# LPCB220_-_CORE_A.net
KiCad netlist of a schematic drawn in Altium Designer
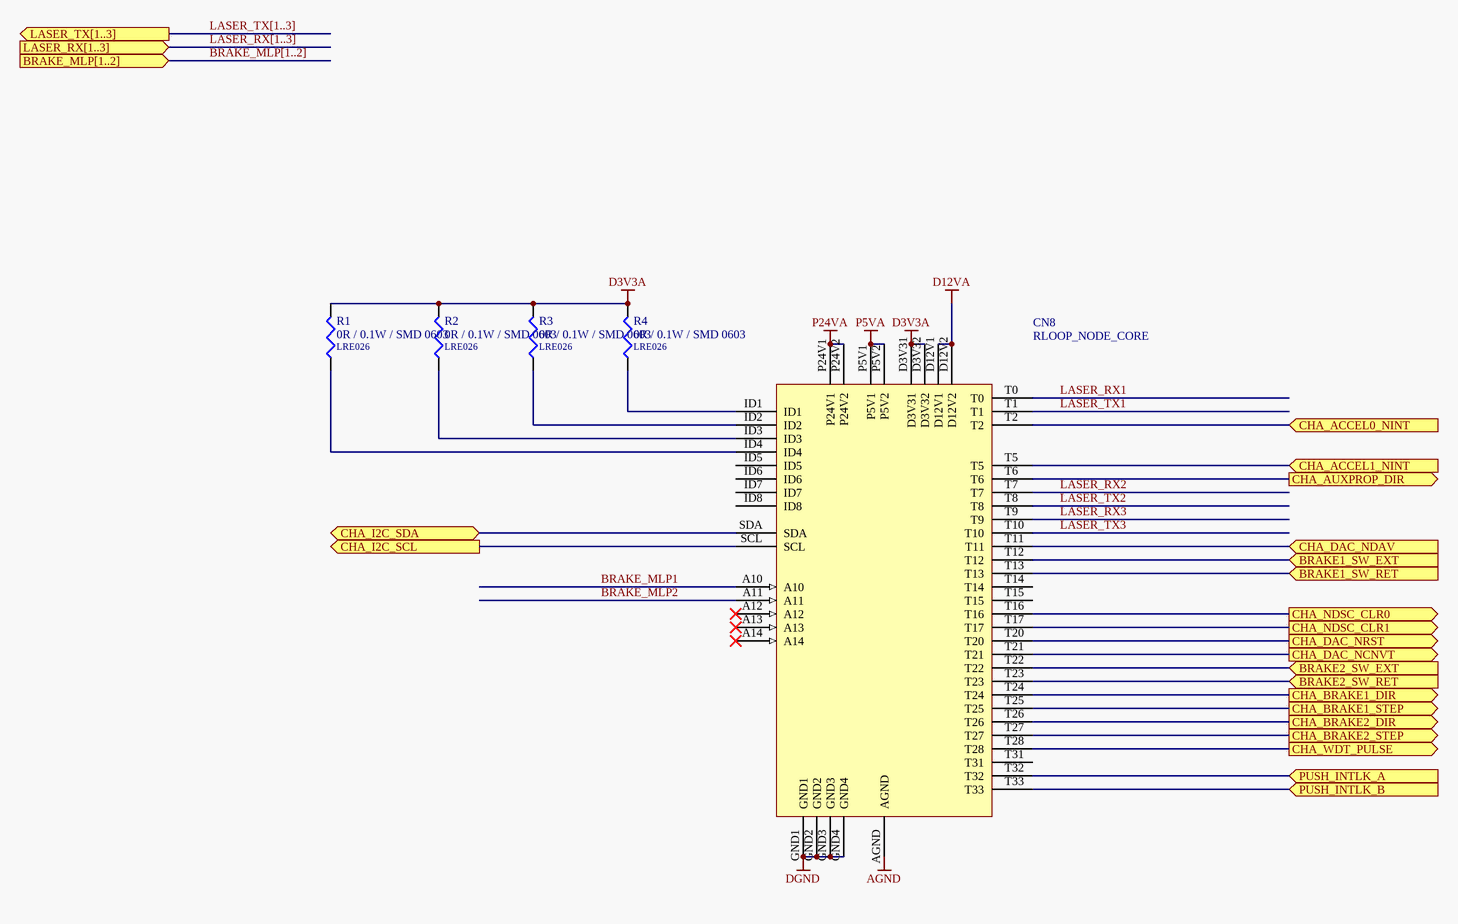
[diagram p0: LPCB220 - CORE A.SchDoc]

(export (version "E")
  (design (tool "Eeschema 10.0.6"))
  (components
    (comp (ref "CN8")
      (value "RLOOP_NODE_CORE")
      (footprint "RLOOP_NODE_CORE")
      (description "rLoop Node Core Connector")
      (libsource (lib "LDL_Connectors") (part "RLOOP_NODE_CORE"))
    )
    (comp (ref "R1")
      (value "0R / 0.1W / SMD 0603")
      (footprint "LFP020__CR1608-0603-IPC7351_B")
      (description "Resistor, Ceramic Chip, 0R, 0.1W, SMD 0603 [LRE026]")
      (fields (field (name "LDL_NUMBER") "LRE026"))
      (libsource (lib "LDL_Resistors") (part "0R / 0.1W / SMD 0603"))
    )
    (comp (ref "R2")
      (value "0R / 0.1W / SMD 0603")
      (footprint "LFP020__CR1608-0603-IPC7351_B")
      (description "Resistor, Ceramic Chip, 0R, 0.1W, SMD 0603 [LRE026]")
      (fields (field (name "LDL_NUMBER") "LRE026"))
      (libsource (lib "LDL_Resistors") (part "0R / 0.1W / SMD 0603"))
    )
    (comp (ref "R3")
      (value "0R / 0.1W / SMD 0603")
      (footprint "LFP020__CR1608-0603-IPC7351_B")
      (description "Resistor, Ceramic Chip, 0R, 0.1W, SMD 0603 [LRE026]")
      (fields (field (name "LDL_NUMBER") "LRE026"))
      (libsource (lib "LDL_Resistors") (part "0R / 0.1W / SMD 0603"))
    )
    (comp (ref "R4")
      (value "0R / 0.1W / SMD 0603")
      (footprint "LFP020__CR1608-0603-IPC7351_B")
      (description "Resistor, Ceramic Chip, 0R, 0.1W, SMD 0603 [LRE026]")
      (fields (field (name "LDL_NUMBER") "LRE026"))
      (libsource (lib "LDL_Resistors") (part "0R / 0.1W / SMD 0603"))
    )
  )
  (nets
    (net (code "1") (name "/BRAKE1_SW_EXT") (class "Default")
      (node (ref "CN8") (pin "T12") (pinfunction "T12_T12") (pintype "passive"))
    )
    (net (code "2") (name "/BRAKE1_SW_RET") (class "Default")
      (node (ref "CN8") (pin "T13") (pinfunction "T13_T13") (pintype "passive"))
    )
    (net (code "3") (name "/BRAKE2_SW_EXT") (class "Default")
      (node (ref "CN8") (pin "T22") (pinfunction "T22_T22") (pintype "passive"))
    )
    (net (code "4") (name "/BRAKE2_SW_RET") (class "Default")
      (node (ref "CN8") (pin "T23") (pinfunction "T23_T23") (pintype "passive"))
    )
    (net (code "5") (name "/BRAKE_MLP1") (class "Default")
      (node (ref "CN8") (pin "A10") (pinfunction "A10_A10") (pintype "input"))
    )
    (net (code "6") (name "/BRAKE_MLP2") (class "Default")
      (node (ref "CN8") (pin "A11") (pinfunction "A11_A11") (pintype "input"))
    )
    (net (code "8") (name "/CHA_ACCEL0_NINT") (class "Default")
      (node (ref "CN8") (pin "T2") (pinfunction "T2_T2") (pintype "passive"))
    )
    (net (code "9") (name "/CHA_ACCEL1_NINT") (class "Default")
      (node (ref "CN8") (pin "T5") (pinfunction "T5_T5") (pintype "passive"))
    )
    (net (code "10") (name "/CHA_AUXPROP_DIR") (class "Default")
      (node (ref "CN8") (pin "T6") (pinfunction "T6_T6") (pintype "passive"))
    )
    (net (code "11") (name "/CHA_BRAKE1_DIR") (class "Default")
      (node (ref "CN8") (pin "T24") (pinfunction "T24_T24") (pintype "passive"))
    )
    (net (code "12") (name "/CHA_BRAKE1_STEP") (class "Default")
      (node (ref "CN8") (pin "T25") (pinfunction "T25_T25") (pintype "passive"))
    )
    (net (code "13") (name "/CHA_BRAKE2_DIR") (class "Default")
      (node (ref "CN8") (pin "T26") (pinfunction "T26_T26") (pintype "passive"))
    )
    (net (code "14") (name "/CHA_BRAKE2_STEP") (class "Default")
      (node (ref "CN8") (pin "T27") (pinfunction "T27_T27") (pintype "passive"))
    )
    (net (code "15") (name "/CHA_DAC_NCNVT") (class "Default")
      (node (ref "CN8") (pin "T21") (pinfunction "T21_T21") (pintype "passive"))
    )
    (net (code "16") (name "/CHA_DAC_NDAV") (class "Default")
      (node (ref "CN8") (pin "T11") (pinfunction "T11_T11") (pintype "passive"))
    )
    (net (code "17") (name "/CHA_DAC_NRST") (class "Default")
      (node (ref "CN8") (pin "T20") (pinfunction "T20_T20") (pintype "passive"))
    )
    (net (code "18") (name "/CHA_I2C_SCL") (class "Default")
      (node (ref "CN8") (pin "SCL") (pinfunction "SCL_SCL") (pintype "passive"))
    )
    (net (code "19") (name "/CHA_I2C_SDA") (class "Default")
      (node (ref "CN8") (pin "SDA") (pinfunction "SDA_SDA") (pintype "passive"))
    )
    (net (code "20") (name "/CHA_NDSC_CLR0") (class "Default")
      (node (ref "CN8") (pin "T16") (pinfunction "T16_T16") (pintype "passive"))
    )
    (net (code "21") (name "/CHA_NDSC_CLR1") (class "Default")
      (node (ref "CN8") (pin "T17") (pinfunction "T17_T17") (pintype "passive"))
    )
    (net (code "22") (name "/CHA_WDT_PULSE") (class "Default")
      (node (ref "CN8") (pin "T28") (pinfunction "T28_T28") (pintype "passive"))
    )
    (net (code "23") (name "/LASER_RX1") (class "Default")
      (node (ref "CN8") (pin "T0") (pinfunction "T0_T0") (pintype "passive"))
    )
    (net (code "24") (name "/LASER_RX2") (class "Default")
      (node (ref "CN8") (pin "T7") (pinfunction "T7_T7") (pintype "passive"))
    )
    (net (code "25") (name "/LASER_RX3") (class "Default")
      (node (ref "CN8") (pin "T9") (pinfunction "T9_T9") (pintype "passive"))
    )
    (net (code "27") (name "/LASER_TX1") (class "Default")
      (node (ref "CN8") (pin "T1") (pinfunction "T1_T1") (pintype "passive"))
    )
    (net (code "28") (name "/LASER_TX2") (class "Default")
      (node (ref "CN8") (pin "T8") (pinfunction "T8_T8") (pintype "passive"))
    )
    (net (code "29") (name "/LASER_TX3") (class "Default")
      (node (ref "CN8") (pin "T10") (pinfunction "T10_T10") (pintype "passive"))
    )
    (net (code "31") (name "/PUSH_INTLK_A") (class "Default")
      (node (ref "CN8") (pin "T32") (pinfunction "T32_T32") (pintype "passive"))
    )
    (net (code "32") (name "/PUSH_INTLK_B") (class "Default")
      (node (ref "CN8") (pin "T33") (pinfunction "T33_T33") (pintype "passive"))
    )
    (net (code "33") (name "AGND") (class "Default")
      (node (ref "CN8") (pin "AGND") (pinfunction "AGND_AGND") (pintype "power_in"))
    )
    (net (code "34") (name "D3V3A") (class "Default")
      (node (ref "CN8") (pin "D3V31") (pinfunction "D3V31_D3V31") (pintype "power_in"))
      (node (ref "CN8") (pin "D3V32") (pinfunction "D3V32_D3V32") (pintype "power_in"))
      (node (ref "R1") (pin "2") (pintype "passive"))
      (node (ref "R2") (pin "2") (pintype "passive"))
      (node (ref "R3") (pin "2") (pintype "passive"))
      (node (ref "R4") (pin "2") (pintype "passive"))
    )
    (net (code "35") (name "D12VA") (class "Default")
      (node (ref "CN8") (pin "D12V1") (pinfunction "D12V1_D12V1") (pintype "power_in"))
      (node (ref "CN8") (pin "D12V2") (pinfunction "D12V2_D12V2") (pintype "power_in"))
    )
    (net (code "36") (name "DGND") (class "Default")
      (node (ref "CN8") (pin "GND1") (pinfunction "GND1_GND1") (pintype "power_in"))
      (node (ref "CN8") (pin "GND2") (pinfunction "GND2_GND2") (pintype "power_in"))
      (node (ref "CN8") (pin "GND3") (pinfunction "GND3_GND3") (pintype "power_in"))
      (node (ref "CN8") (pin "GND4") (pinfunction "GND4_GND4") (pintype "power_in"))
    )
    (net (code "37") (name "Net-(CN8-PadID1)") (class "Default")
      (node (ref "CN8") (pin "ID1") (pinfunction "ID1_ID1") (pintype "passive"))
      (node (ref "R4") (pin "1") (pintype "passive"))
    )
    (net (code "38") (name "Net-(CN8-PadID2)") (class "Default")
      (node (ref "CN8") (pin "ID2") (pinfunction "ID2_ID2") (pintype "passive"))
      (node (ref "R3") (pin "1") (pintype "passive"))
    )
    (net (code "39") (name "Net-(CN8-PadID3)") (class "Default")
      (node (ref "CN8") (pin "ID3") (pinfunction "ID3_ID3") (pintype "passive"))
      (node (ref "R2") (pin "1") (pintype "passive"))
    )
    (net (code "40") (name "Net-(CN8-PadID4)") (class "Default")
      (node (ref "CN8") (pin "ID4") (pinfunction "ID4_ID4") (pintype "passive"))
      (node (ref "R1") (pin "1") (pintype "passive"))
    )
    (net (code "41") (name "P5VA") (class "Default")
      (node (ref "CN8") (pin "P5V1") (pinfunction "P5V1_P5V1") (pintype "power_in"))
      (node (ref "CN8") (pin "P5V2") (pinfunction "P5V2_P5V2") (pintype "power_in"))
    )
    (net (code "42") (name "P24VA") (class "Default")
      (node (ref "CN8") (pin "P24V1") (pinfunction "P24V1_P24V1") (pintype "power_in"))
      (node (ref "CN8") (pin "P24V2") (pinfunction "P24V2_P24V2") (pintype "power_in"))
    )
    (net (code "43") (name "unconnected-(CN8-PadA12)") (class "Default")
      (node (ref "CN8") (pin "A12") (pinfunction "A12_A12") (pintype "input+no_connect"))
    )
    (net (code "44") (name "unconnected-(CN8-PadA13)") (class "Default")
      (node (ref "CN8") (pin "A13") (pinfunction "A13_A13") (pintype "input+no_connect"))
    )
    (net (code "45") (name "unconnected-(CN8-PadA14)") (class "Default")
      (node (ref "CN8") (pin "A14") (pinfunction "A14_A14") (pintype "input+no_connect"))
    )
    (net (code "46") (name "unconnected-(CN8-PadID5)") (class "Default")
      (node (ref "CN8") (pin "ID5") (pinfunction "ID5_ID5") (pintype "passive"))
    )
    (net (code "47") (name "unconnected-(CN8-PadID6)") (class "Default")
      (node (ref "CN8") (pin "ID6") (pinfunction "ID6_ID6") (pintype "passive"))
    )
    (net (code "48") (name "unconnected-(CN8-PadID7)") (class "Default")
      (node (ref "CN8") (pin "ID7") (pinfunction "ID7_ID7") (pintype "passive"))
    )
    (net (code "49") (name "unconnected-(CN8-PadID8)") (class "Default")
      (node (ref "CN8") (pin "ID8") (pinfunction "ID8_ID8") (pintype "passive"))
    )
    (net (code "50") (name "unconnected-(CN8-PadT14)") (class "Default")
      (node (ref "CN8") (pin "T14") (pinfunction "T14_T14") (pintype "passive"))
    )
    (net (code "51") (name "unconnected-(CN8-PadT15)") (class "Default")
      (node (ref "CN8") (pin "T15") (pinfunction "T15_T15") (pintype "passive"))
    )
    (net (code "52") (name "unconnected-(CN8-PadT31)") (class "Default")
      (node (ref "CN8") (pin "T31") (pinfunction "T31_T31") (pintype "passive"))
    )
  )
)
